# 8LedBoard.net
KiCad netlist of a schematic drawn in EAGLE
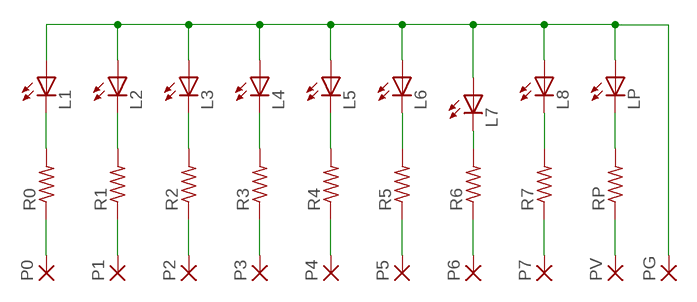
[diagram p0: schematic, sheet 1]

(export (version "E")
  (design (tool "Eeschema 10.0.6"))
  (components
    (comp (ref "L1")
      (value "LED5MM")
      (footprint "eagle-import:LED5MM")
      (libsource (lib "eagle-import") (part "LED5MM"))
    )
    (comp (ref "L2")
      (value "LED5MM")
      (footprint "eagle-import:LED5MM")
      (libsource (lib "eagle-import") (part "LED5MM"))
    )
    (comp (ref "L3")
      (value "LED5MM")
      (footprint "eagle-import:LED5MM")
      (libsource (lib "eagle-import") (part "LED5MM"))
    )
    (comp (ref "L4")
      (value "LED5MM")
      (footprint "eagle-import:LED5MM")
      (libsource (lib "eagle-import") (part "LED5MM"))
    )
    (comp (ref "L5")
      (value "LED5MM")
      (footprint "eagle-import:LED5MM")
      (libsource (lib "eagle-import") (part "LED5MM"))
    )
    (comp (ref "L6")
      (value "LED5MM")
      (footprint "eagle-import:LED5MM")
      (libsource (lib "eagle-import") (part "LED5MM"))
    )
    (comp (ref "L7")
      (value "LED5MM")
      (footprint "eagle-import:LED5MM")
      (libsource (lib "eagle-import") (part "LED5MM"))
    )
    (comp (ref "L8")
      (value "LED5MM")
      (footprint "eagle-import:LED5MM")
      (libsource (lib "eagle-import") (part "LED5MM"))
    )
    (comp (ref "LP")
      (value "LED5MM")
      (footprint "eagle-import:LED5MM")
      (libsource (lib "eagle-import") (part "LED5MM"))
    )
    (comp (ref "P0")
      (value "1,6/0,9")
      (footprint "eagle-import:1,6_0,9")
      (libsource (lib "eagle-import") (part "1,6/0,9"))
    )
    (comp (ref "P1")
      (value "1,6/0,9")
      (footprint "eagle-import:1,6_0,9")
      (libsource (lib "eagle-import") (part "1,6/0,9"))
    )
    (comp (ref "P2")
      (value "1,6/0,9")
      (footprint "eagle-import:1,6_0,9")
      (libsource (lib "eagle-import") (part "1,6/0,9"))
    )
    (comp (ref "P3")
      (value "1,6/0,9")
      (footprint "eagle-import:1,6_0,9")
      (libsource (lib "eagle-import") (part "1,6/0,9"))
    )
    (comp (ref "P4")
      (value "1,6/0,9")
      (footprint "eagle-import:1,6_0,9")
      (libsource (lib "eagle-import") (part "1,6/0,9"))
    )
    (comp (ref "P5")
      (value "1,6/0,9")
      (footprint "eagle-import:1,6_0,9")
      (libsource (lib "eagle-import") (part "1,6/0,9"))
    )
    (comp (ref "P6")
      (value "1,6/0,9")
      (footprint "eagle-import:1,6_0,9")
      (libsource (lib "eagle-import") (part "1,6/0,9"))
    )
    (comp (ref "P7")
      (value "1,6/0,9")
      (footprint "eagle-import:1,6_0,9")
      (libsource (lib "eagle-import") (part "1,6/0,9"))
    )
    (comp (ref "PG")
      (value "1,6/0,9")
      (footprint "eagle-import:1,6_0,9")
      (libsource (lib "eagle-import") (part "1,6/0,9"))
    )
    (comp (ref "PV")
      (value "1,6/0,9")
      (footprint "eagle-import:1,6_0,9")
      (libsource (lib "eagle-import") (part "1,6/0,9"))
    )
    (comp (ref "R0")
      (value "R-US_0207/10")
      (footprint "eagle-import:0207_10")
      (libsource (lib "eagle-import") (part "R-US_0207/10"))
    )
    (comp (ref "R1")
      (value "R-US_0207/10")
      (footprint "eagle-import:0207_10")
      (libsource (lib "eagle-import") (part "R-US_0207/10"))
    )
    (comp (ref "R2")
      (value "R-US_0207/10")
      (footprint "eagle-import:0207_10")
      (libsource (lib "eagle-import") (part "R-US_0207/10"))
    )
    (comp (ref "R3")
      (value "R-US_0207/10")
      (footprint "eagle-import:0207_10")
      (libsource (lib "eagle-import") (part "R-US_0207/10"))
    )
    (comp (ref "R4")
      (value "R-US_0207/10")
      (footprint "eagle-import:0207_10")
      (libsource (lib "eagle-import") (part "R-US_0207/10"))
    )
    (comp (ref "R5")
      (value "R-US_0207/10")
      (footprint "eagle-import:0207_10")
      (libsource (lib "eagle-import") (part "R-US_0207/10"))
    )
    (comp (ref "R6")
      (value "R-US_0207/10")
      (footprint "eagle-import:0207_10")
      (libsource (lib "eagle-import") (part "R-US_0207/10"))
    )
    (comp (ref "R7")
      (value "R-US_0207/10")
      (footprint "eagle-import:0207_10")
      (libsource (lib "eagle-import") (part "R-US_0207/10"))
    )
    (comp (ref "RP")
      (value "R-US_0207/10")
      (footprint "eagle-import:0207_10")
      (libsource (lib "eagle-import") (part "R-US_0207/10"))
    )
  )
  (nets
    (net (code "1") (name "Net-(L1-C)") (class "Default")
      (node (ref "L1") (pin "K") (pinfunction "C_K") (pintype "passive"))
      (node (ref "R0") (pin "2") (pinfunction "2_2") (pintype "passive"))
    )
    (net (code "2") (name "Net-(L2-C)") (class "Default")
      (node (ref "L2") (pin "K") (pinfunction "C_K") (pintype "passive"))
      (node (ref "R1") (pin "2") (pinfunction "2_2") (pintype "passive"))
    )
    (net (code "3") (name "Net-(L3-C)") (class "Default")
      (node (ref "L3") (pin "K") (pinfunction "C_K") (pintype "passive"))
      (node (ref "R2") (pin "2") (pinfunction "2_2") (pintype "passive"))
    )
    (net (code "4") (name "Net-(L4-C)") (class "Default")
      (node (ref "L4") (pin "K") (pinfunction "C_K") (pintype "passive"))
      (node (ref "R3") (pin "2") (pinfunction "2_2") (pintype "passive"))
    )
    (net (code "5") (name "Net-(L5-C)") (class "Default")
      (node (ref "L5") (pin "K") (pinfunction "C_K") (pintype "passive"))
      (node (ref "R4") (pin "2") (pinfunction "2_2") (pintype "passive"))
    )
    (net (code "6") (name "Net-(L6-C)") (class "Default")
      (node (ref "L6") (pin "K") (pinfunction "C_K") (pintype "passive"))
      (node (ref "R5") (pin "2") (pinfunction "2_2") (pintype "passive"))
    )
    (net (code "7") (name "Net-(L7-C)") (class "Default")
      (node (ref "L7") (pin "K") (pinfunction "C_K") (pintype "passive"))
      (node (ref "R6") (pin "2") (pinfunction "2_2") (pintype "passive"))
    )
    (net (code "8") (name "Net-(L8-C)") (class "Default")
      (node (ref "L8") (pin "K") (pinfunction "C_K") (pintype "passive"))
      (node (ref "R7") (pin "2") (pinfunction "2_2") (pintype "passive"))
    )
    (net (code "9") (name "Net-(LP-C)") (class "Default")
      (node (ref "LP") (pin "K") (pinfunction "C_K") (pintype "passive"))
      (node (ref "RP") (pin "2") (pinfunction "2_2") (pintype "passive"))
    )
    (net (code "10") (name "Net-(P0-P)") (class "Default")
      (node (ref "P0") (pin "1") (pinfunction "P_1") (pintype "passive"))
      (node (ref "R0") (pin "1") (pinfunction "1_1") (pintype "passive"))
    )
    (net (code "11") (name "Net-(P1-P)") (class "Default")
      (node (ref "P1") (pin "1") (pinfunction "P_1") (pintype "passive"))
      (node (ref "R1") (pin "1") (pinfunction "1_1") (pintype "passive"))
    )
    (net (code "12") (name "Net-(P2-P)") (class "Default")
      (node (ref "P2") (pin "1") (pinfunction "P_1") (pintype "passive"))
      (node (ref "R2") (pin "1") (pinfunction "1_1") (pintype "passive"))
    )
    (net (code "13") (name "Net-(P3-P)") (class "Default")
      (node (ref "P3") (pin "1") (pinfunction "P_1") (pintype "passive"))
      (node (ref "R3") (pin "1") (pinfunction "1_1") (pintype "passive"))
    )
    (net (code "14") (name "Net-(P4-P)") (class "Default")
      (node (ref "P4") (pin "1") (pinfunction "P_1") (pintype "passive"))
      (node (ref "R4") (pin "1") (pinfunction "1_1") (pintype "passive"))
    )
    (net (code "15") (name "Net-(P5-P)") (class "Default")
      (node (ref "P5") (pin "1") (pinfunction "P_1") (pintype "passive"))
      (node (ref "R5") (pin "1") (pinfunction "1_1") (pintype "passive"))
    )
    (net (code "16") (name "Net-(P6-P)") (class "Default")
      (node (ref "P6") (pin "1") (pinfunction "P_1") (pintype "passive"))
      (node (ref "R6") (pin "1") (pinfunction "1_1") (pintype "passive"))
    )
    (net (code "17") (name "Net-(P7-P)") (class "Default")
      (node (ref "P7") (pin "1") (pinfunction "P_1") (pintype "passive"))
      (node (ref "R7") (pin "1") (pinfunction "1_1") (pintype "passive"))
    )
    (net (code "18") (name "Net-(PG-P)") (class "Default")
      (node (ref "L1") (pin "A") (pinfunction "A_A") (pintype "passive"))
      (node (ref "L2") (pin "A") (pinfunction "A_A") (pintype "passive"))
      (node (ref "L3") (pin "A") (pinfunction "A_A") (pintype "passive"))
      (node (ref "L4") (pin "A") (pinfunction "A_A") (pintype "passive"))
      (node (ref "L5") (pin "A") (pinfunction "A_A") (pintype "passive"))
      (node (ref "L6") (pin "A") (pinfunction "A_A") (pintype "passive"))
      (node (ref "L7") (pin "A") (pinfunction "A_A") (pintype "passive"))
      (node (ref "L8") (pin "A") (pinfunction "A_A") (pintype "passive"))
      (node (ref "LP") (pin "A") (pinfunction "A_A") (pintype "passive"))
      (node (ref "PG") (pin "1") (pinfunction "P_1") (pintype "passive"))
    )
    (net (code "19") (name "Net-(PV-P)") (class "Default")
      (node (ref "PV") (pin "1") (pinfunction "P_1") (pintype "passive"))
      (node (ref "RP") (pin "1") (pinfunction "1_1") (pintype "passive"))
    )
  )
)
